# PhatStats_Slim_Enclosure_ESP_Lolin_D32_X.net
KiCad netlist of a schematic drawn in EAGLE
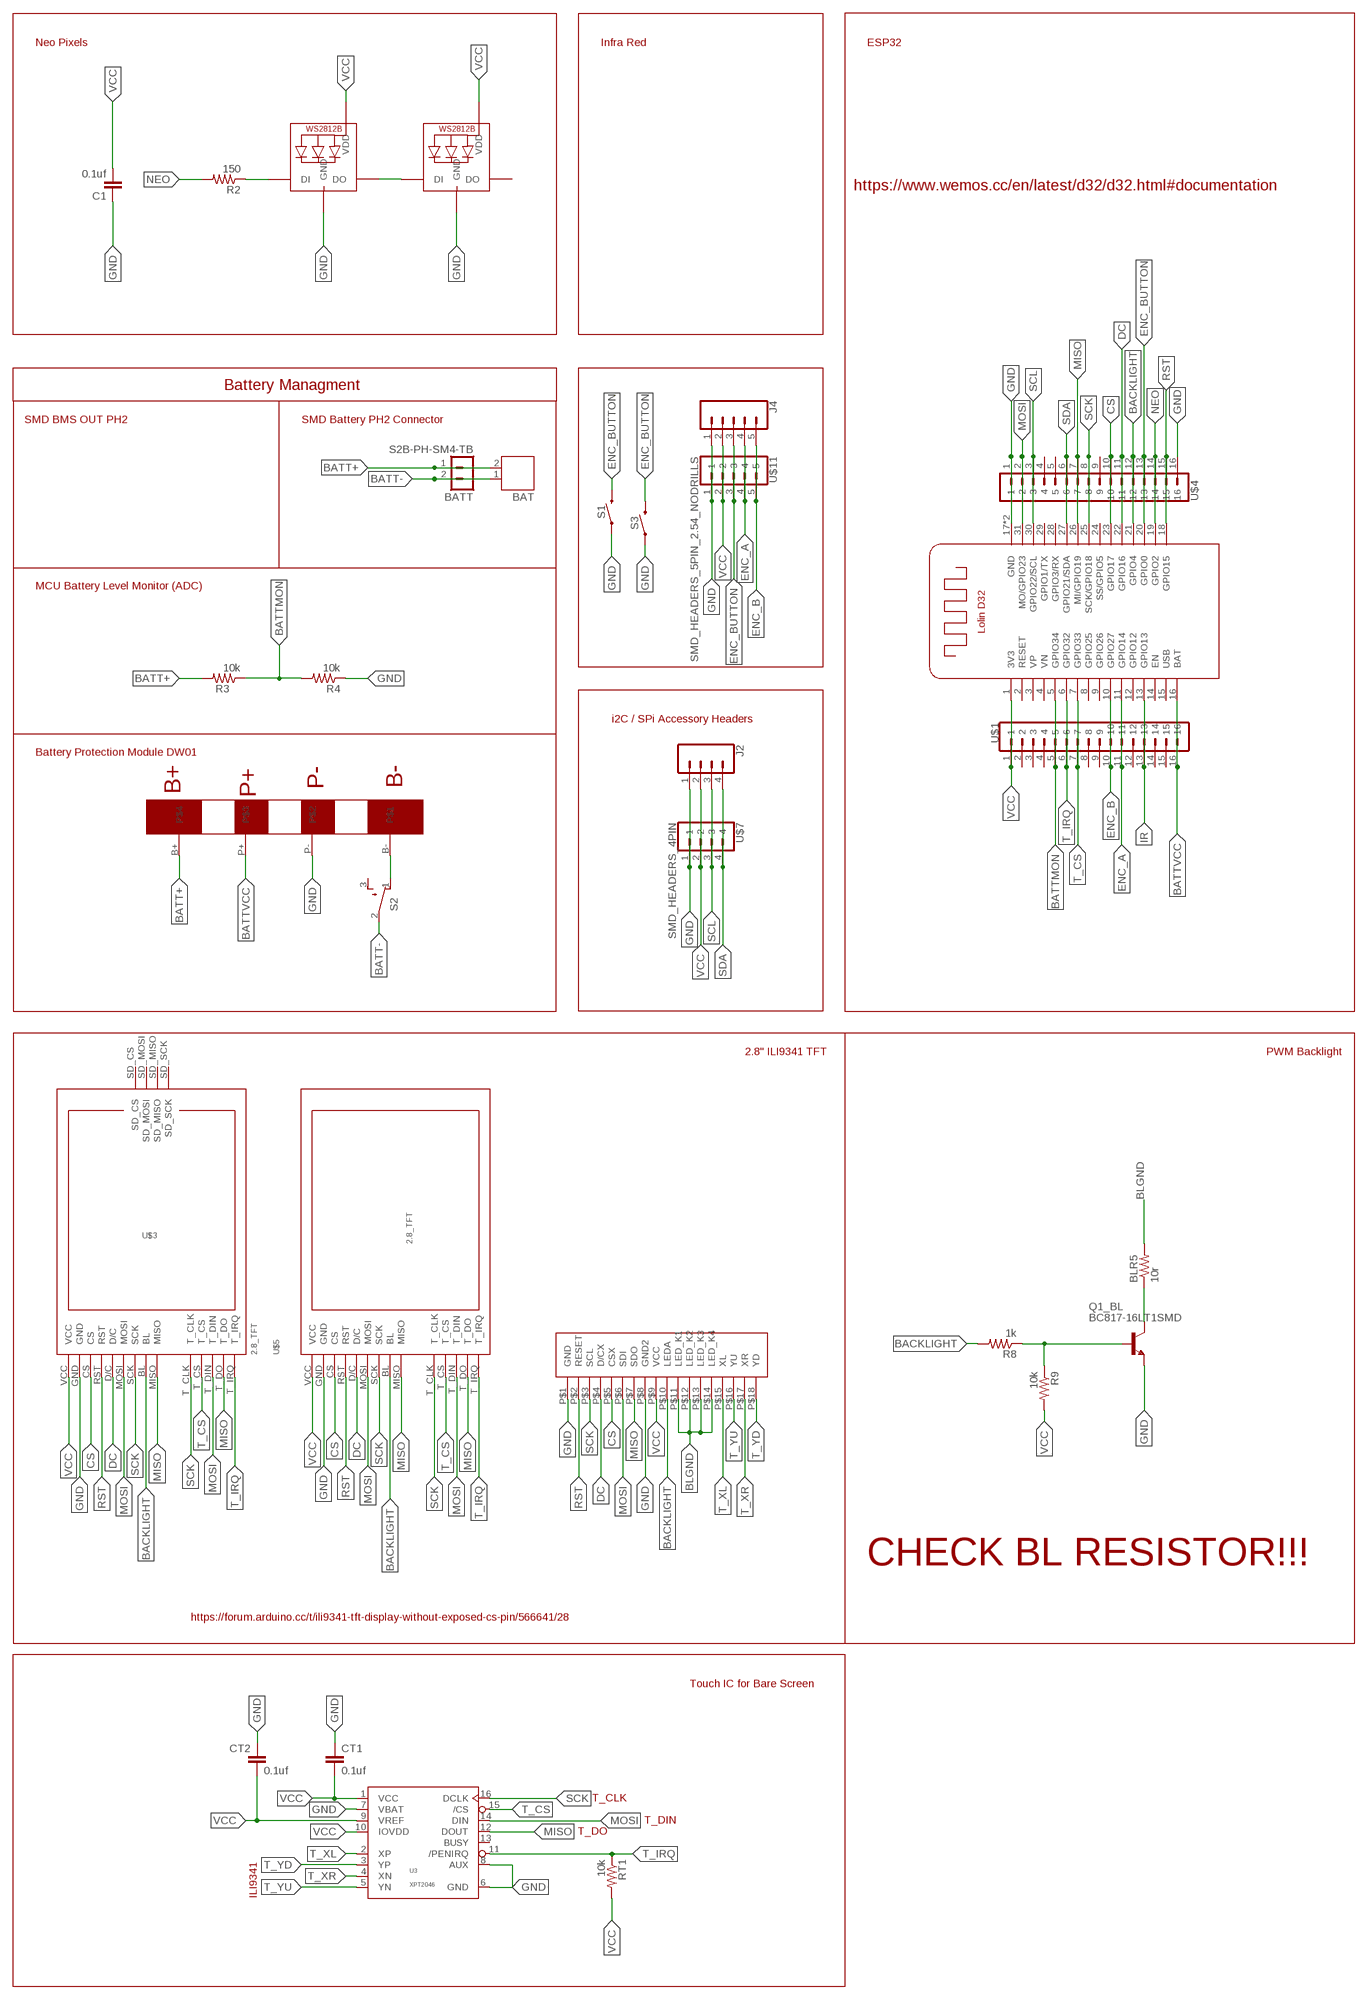
[diagram p0: schematic, sheet 1]

(export (version "E")
  (design (tool "Eeschema 10.0.6"))
  (components
    (comp (ref "0")
      (value "ILI9341-2.8")
      (footprint "eagle-import:ILI9341-2.8")
      (libsource (lib "eagle-import") (part "ILI9341-2.8"))
    )
    (comp (ref "BAT")
      (value "JST-PH2")
      (footprint "eagle-import:JST-PH2")
      (libsource (lib "eagle-import") (part "JST-PH2"))
    )
    (comp (ref "BATT")
      (value "S2B-PH-SM4-TB")
      (footprint "eagle-import:S2B-PH-SM4-TB")
      (libsource (lib "eagle-import") (part "S2B-PH-SM4-TB"))
    )
    (comp (ref "BLR5")
      (value "10r")
      (footprint "eagle-import:M1206")
      (libsource (lib "eagle-import") (part "R-US_M1206"))
    )
    (comp (ref "BMS")
      (value "DW01BATTERYPROT")
      (footprint "eagle-import:DW01BATTERYPROT")
      (libsource (lib "eagle-import") (part "DW01BATTERYPROT"))
    )
    (comp (ref "C1")
      (value "0.1uf")
      (footprint "eagle-import:C1206")
      (libsource (lib "eagle-import") (part "C-EUC1206"))
    )
    (comp (ref "CT1")
      (value "0.1uf")
      (footprint "eagle-import:C1206")
      (libsource (lib "eagle-import") (part "C-EUC1206"))
    )
    (comp (ref "CT2")
      (value "0.1uf")
      (footprint "eagle-import:C1206")
      (libsource (lib "eagle-import") (part "C-EUC1206"))
    )
    (comp (ref "J2")
      (value "CONN_04PTH")
      (footprint "eagle-import:1X04")
      (libsource (lib "eagle-import") (part "CONN_04PTH"))
    )
    (comp (ref "J4")
      (value "CONN_05")
      (footprint "eagle-import:1X05")
      (libsource (lib "eagle-import") (part "CONN_05"))
    )
    (comp (ref "NEO1")
      (value "WS2812B5050")
      (footprint "eagle-import:WS2812B")
      (libsource (lib "eagle-import") (part "WS2812B5050"))
    )
    (comp (ref "NEO2")
      (value "WS2812B5050")
      (footprint "eagle-import:WS2812B")
      (libsource (lib "eagle-import") (part "WS2812B5050"))
    )
    (comp (ref "Q1_BL")
      (value "BC817-16LT1SMD")
      (footprint "eagle-import:SOT23-BEC")
      (libsource (lib "eagle-import") (part "BC817SMD-16LT1"))
    )
    (comp (ref "R2")
      (value "150")
      (footprint "eagle-import:M1206")
      (libsource (lib "eagle-import") (part "R-US_M1206"))
    )
    (comp (ref "R3")
      (value "10k")
      (footprint "eagle-import:M1206")
      (libsource (lib "eagle-import") (part "R-US_M1206"))
    )
    (comp (ref "R4")
      (value "10k")
      (footprint "eagle-import:M1206")
      (libsource (lib "eagle-import") (part "R-US_M1206"))
    )
    (comp (ref "R8")
      (value "1k")
      (footprint "eagle-import:M1206")
      (libsource (lib "eagle-import") (part "R-US_M1206"))
    )
    (comp (ref "R9")
      (value "10k")
      (footprint "eagle-import:M1206")
      (libsource (lib "eagle-import") (part "R-US_M1206"))
    )
    (comp (ref "RT1")
      (value "10k")
      (footprint "eagle-import:M1206")
      (libsource (lib "eagle-import") (part "R-US_M1206"))
    )
    (comp (ref "S1")
      (value "MOMENTARY-SWITCH-SPST-PTH-6.0MM")
      (footprint "eagle-import:TACTILE_SWITCH_PTH_6.0MM")
      (libsource (lib "eagle-import") (part "MOMENTARY-SWITCH-SPST-PTH-6.0MM"))
    )
    (comp (ref "S2")
      (value "SK-12F14(1P2T)0.5A50VDC3MMPITCH")
      (footprint "eagle-import:SK-12F14(1P2T)0.5A50VDC3MMPITCH")
      (libsource (lib "eagle-import") (part "SK-12F14(1P2T)0.5A50VDC3MMPITCH"))
    )
    (comp (ref "S3")
      (value "MOMENTARY-SWITCH-SPST-SMD-6.2MM-TALL")
      (footprint "eagle-import:TACTILE_SWITCH_SMD_6.2MM_TALL")
      (libsource (lib "eagle-import") (part "MOMENTARY-SWITCH-SPST-SMD-6.2MM-TALL"))
    )
    (comp (ref "U$1")
      (value "SMD_HEADERS_16PIN_2.54_NODRILLSSMD_HEADERS_16PIN")
      (footprint "eagle-import:SMD_HEADERS_16PIN")
      (libsource (lib "eagle-import") (part "SMD_HEADERS_16PIN_2.54_NODRILLSSMD_HEADERS_16PIN"))
    )
    (comp (ref "U$2")
      (value "TML_LOLIND32")
      (footprint "eagle-import:TML_LOLIND32")
      (libsource (lib "eagle-import") (part "TML_LOLIND32"))
    )
    (comp (ref "U$3")
      (value "2.8_TFT")
      (footprint "eagle-import:2.8_TFT")
      (libsource (lib "eagle-import") (part "2.8_TFT"))
    )
    (comp (ref "U$4")
      (value "SMD_HEADERS_16PIN_2.54_NODRILLSSMD_HEADERS_16PIN")
      (footprint "eagle-import:SMD_HEADERS_16PIN")
      (libsource (lib "eagle-import") (part "SMD_HEADERS_16PIN_2.54_NODRILLSSMD_HEADERS_16PIN"))
    )
    (comp (ref "U$5")
      (value "2.8_TFT")
      (footprint "eagle-import:2.8_TFT")
      (libsource (lib "eagle-import") (part "TML_ili9341-2.8_tft-display_PinHeader only_2.8_TFT"))
    )
    (comp (ref "U$7")
      (value "SMD_HEADERS_4PIN")
      (footprint "eagle-import:SMD_HEADERS_4PIN")
      (libsource (lib "eagle-import") (part "SMD_HEADERS_4PIN"))
    )
    (comp (ref "U$11")
      (value "SMD_HEADERS_5PIN_2.54_NODRILLS")
      (footprint "eagle-import:SMD_HEADERS_5PIN")
      (libsource (lib "eagle-import") (part "SMD_HEADERS_5PIN_2.54_NODRILLS"))
    )
    (comp (ref "U3")
      (value "XPT2046")
      (footprint "eagle-import:TSSOP-16")
      (fields (field (name "MF") "Xptek"))
      (libsource (lib "eagle-import") (part "XPT2046"))
    )
  )
  (nets
    (net (code "1") (name "/USB") (class "Default")
      (node (ref "U$2") (pin "15") (pinfunction "USB_15") (pintype "power_in"))
    )
    (net (code "2") (name "BACKLIGHT") (class "Default")
      (node (ref "0") (pin "P$10") (pinfunction "LEDA_P$10") (pintype "bidirectional"))
      (node (ref "R8") (pin "2") (pinfunction "2_2") (pintype "passive"))
      (node (ref "U$2") (pin "21") (pinfunction "GPIO4_21") (pintype "bidirectional"))
      (node (ref "U$3") (pin "BL") (pinfunction "BL_BL") (pintype "bidirectional"))
      (node (ref "U$4") (pin "12") (pinfunction "12_12") (pintype "passive"))
      (node (ref "U$5") (pin "BL") (pinfunction "BL_BL") (pintype "bidirectional"))
    )
    (net (code "3") (name "BATT+") (class "Default")
      (node (ref "BAT") (pin "2") (pinfunction "2_2") (pintype "passive"))
      (node (ref "BATT") (pin "1") (pinfunction "1_1") (pintype "passive"))
      (node (ref "BMS") (pin "B+") (pinfunction "P$4_B+") (pintype "bidirectional"))
      (node (ref "R3") (pin "2") (pinfunction "2_2") (pintype "passive"))
    )
    (net (code "4") (name "BATT-") (class "Default")
      (node (ref "BAT") (pin "1") (pinfunction "1_1") (pintype "passive"))
      (node (ref "BATT") (pin "2") (pinfunction "2_2") (pintype "passive"))
      (node (ref "S2") (pin "2") (pinfunction "P_2") (pintype "passive"))
    )
    (net (code "5") (name "BATTMON") (class "Default")
      (node (ref "R3") (pin "1") (pinfunction "1_1") (pintype "passive"))
      (node (ref "R4") (pin "2") (pinfunction "2_2") (pintype "passive"))
      (node (ref "U$1") (pin "5") (pinfunction "5_5") (pintype "passive"))
      (node (ref "U$2") (pin "5") (pinfunction "GPIO34_5") (pintype "input"))
    )
    (net (code "6") (name "BATTVCC") (class "Default")
      (node (ref "BMS") (pin "P+") (pinfunction "P$3_P+") (pintype "bidirectional"))
      (node (ref "U$1") (pin "16") (pinfunction "16_16") (pintype "passive"))
      (node (ref "U$2") (pin "16") (pinfunction "BAT_16") (pintype "power_in"))
    )
    (net (code "7") (name "BLGND") (class "Default")
      (node (ref "0") (pin "P$11") (pinfunction "LED_K1_P$11") (pintype "bidirectional"))
      (node (ref "0") (pin "P$12") (pinfunction "LED_K2_P$12") (pintype "bidirectional"))
      (node (ref "0") (pin "P$13") (pinfunction "LED_K3_P$13") (pintype "bidirectional"))
      (node (ref "0") (pin "P$14") (pinfunction "LED_K4_P$14") (pintype "bidirectional"))
      (node (ref "BLR5") (pin "2") (pinfunction "2_2") (pintype "passive"))
    )
    (net (code "8") (name "CS") (class "Default")
      (node (ref "0") (pin "P$5") (pinfunction "CSX_P$5") (pintype "bidirectional"))
      (node (ref "U$2") (pin "23") (pinfunction "GPIO17_23") (pintype "bidirectional"))
      (node (ref "U$3") (pin "CS") (pinfunction "CS_CS") (pintype "bidirectional"))
      (node (ref "U$4") (pin "10") (pinfunction "10_10") (pintype "passive"))
      (node (ref "U$5") (pin "CS") (pinfunction "CS_CS") (pintype "bidirectional"))
    )
    (net (code "9") (name "DC") (class "Default")
      (node (ref "0") (pin "P$4") (pinfunction "D/CX_P$4") (pintype "bidirectional"))
      (node (ref "U$2") (pin "22") (pinfunction "GPIO16_22") (pintype "bidirectional"))
      (node (ref "U$3") (pin "D/C") (pinfunction "D/C_D/C") (pintype "bidirectional"))
      (node (ref "U$4") (pin "11") (pinfunction "11_11") (pintype "passive"))
      (node (ref "U$5") (pin "D/C") (pinfunction "D/C_D/C") (pintype "bidirectional"))
    )
    (net (code "10") (name "ENC_A") (class "Default")
      (node (ref "J4") (pin "4") (pinfunction "4_4") (pintype "passive"))
      (node (ref "U$1") (pin "11") (pinfunction "11_11") (pintype "passive"))
      (node (ref "U$11") (pin "4") (pinfunction "4_4") (pintype "passive"))
      (node (ref "U$2") (pin "11") (pinfunction "GPIO14_11") (pintype "bidirectional"))
    )
    (net (code "11") (name "ENC_B") (class "Default")
      (node (ref "J4") (pin "5") (pinfunction "5_5") (pintype "passive"))
      (node (ref "U$1") (pin "10") (pinfunction "10_10") (pintype "passive"))
      (node (ref "U$11") (pin "5") (pinfunction "5_5") (pintype "passive"))
      (node (ref "U$2") (pin "10") (pinfunction "GPIO27_10") (pintype "bidirectional"))
    )
    (net (code "12") (name "ENC_BUTTON") (class "Default")
      (node (ref "J4") (pin "3") (pinfunction "3_3") (pintype "passive"))
      (node (ref "S1") (pin "3") (pinfunction "2_3") (pintype "passive"))
      (node (ref "S3") (pin "B2") (pinfunction "2_B2") (pintype "passive"))
      (node (ref "U$11") (pin "3") (pinfunction "3_3") (pintype "passive"))
      (node (ref "U$2") (pin "20") (pinfunction "GPIO0_20") (pintype "bidirectional"))
      (node (ref "U$4") (pin "13") (pinfunction "13_13") (pintype "passive"))
    )
    (net (code "13") (name "GND") (class "Default")
      (node (ref "0") (pin "P$1") (pinfunction "GND_P$1") (pintype "bidirectional"))
      (node (ref "0") (pin "P$8") (pinfunction "GND2_P$8") (pintype "bidirectional"))
      (node (ref "BMS") (pin "P-") (pinfunction "P$2_P-") (pintype "bidirectional"))
      (node (ref "C1") (pin "1") (pinfunction "1_1") (pintype "passive"))
      (node (ref "CT1") (pin "1") (pinfunction "1_1") (pintype "passive"))
      (node (ref "CT2") (pin "1") (pinfunction "1_1") (pintype "passive"))
      (node (ref "J2") (pin "1") (pinfunction "1_1") (pintype "passive"))
      (node (ref "J4") (pin "1") (pinfunction "1_1") (pintype "passive"))
      (node (ref "NEO1") (pin "3-GND") (pinfunction "GND_3-GND") (pintype "power_in"))
      (node (ref "NEO2") (pin "3-GND") (pinfunction "GND_3-GND") (pintype "power_in"))
      (node (ref "Q1_BL") (pin "E") (pinfunction "E_E") (pintype "passive"))
      (node (ref "R4") (pin "1") (pinfunction "1_1") (pintype "passive"))
      (node (ref "S1") (pin "1") (pinfunction "1_1") (pintype "passive"))
      (node (ref "S3") (pin "A2") (pinfunction "1_A2") (pintype "passive"))
      (node (ref "U$11") (pin "1") (pinfunction "1_1") (pintype "passive"))
      (node (ref "U$2") (pin "17") (pinfunction "GND_17") (pintype "power_in"))
      (node (ref "U$2") (pin "32") (pinfunction "GND_32") (pintype "power_in"))
      (node (ref "U$3") (pin "GND") (pinfunction "GND_GND") (pintype "bidirectional"))
      (node (ref "U$4") (pin "1") (pinfunction "1_1") (pintype "passive"))
      (node (ref "U$4") (pin "16") (pinfunction "16_16") (pintype "passive"))
      (node (ref "U$5") (pin "GND") (pinfunction "GND_GND") (pintype "bidirectional"))
      (node (ref "U$7") (pin "1") (pinfunction "1_1") (pintype "passive"))
      (node (ref "U3") (pin "6") (pinfunction "GND_6") (pintype "power_in"))
      (node (ref "U3") (pin "7") (pinfunction "VBAT_7") (pintype "input"))
      (node (ref "U3") (pin "8") (pinfunction "AUX_8") (pintype "input"))
    )
    (net (code "14") (name "IR") (class "Default")
      (node (ref "U$1") (pin "13") (pinfunction "13_13") (pintype "passive"))
      (node (ref "U$2") (pin "13") (pinfunction "GPIO13_13") (pintype "bidirectional"))
    )
    (net (code "15") (name "MISO") (class "Default")
      (node (ref "0") (pin "P$7") (pinfunction "SDO_P$7") (pintype "bidirectional"))
      (node (ref "U$2") (pin "26") (pinfunction "MI/GPIO19_26") (pintype "bidirectional"))
      (node (ref "U$3") (pin "MISO") (pinfunction "MISO_MISO") (pintype "bidirectional"))
      (node (ref "U$3") (pin "T_DO") (pinfunction "T_DO_T_DO") (pintype "bidirectional"))
      (node (ref "U$4") (pin "7") (pinfunction "7_7") (pintype "passive"))
      (node (ref "U$5") (pin "MISO") (pinfunction "MISO_MISO") (pintype "bidirectional"))
      (node (ref "U$5") (pin "T_DO") (pinfunction "T_DO_T_DO") (pintype "bidirectional"))
      (node (ref "U3") (pin "12") (pinfunction "DOUT_12") (pintype "output"))
    )
    (net (code "16") (name "MOSI") (class "Default")
      (node (ref "0") (pin "P$6") (pinfunction "SDI_P$6") (pintype "bidirectional"))
      (node (ref "U$2") (pin "31") (pinfunction "MO/GPIO23_31") (pintype "bidirectional"))
      (node (ref "U$3") (pin "MOSI") (pinfunction "MOSI_MOSI") (pintype "bidirectional"))
      (node (ref "U$3") (pin "T_DIN") (pinfunction "T_DIN_T_DIN") (pintype "bidirectional"))
      (node (ref "U$4") (pin "2") (pinfunction "2_2") (pintype "passive"))
      (node (ref "U$5") (pin "MOSI") (pinfunction "MOSI_MOSI") (pintype "bidirectional"))
      (node (ref "U$5") (pin "T_DIN") (pinfunction "T_DIN_T_DIN") (pintype "bidirectional"))
      (node (ref "U3") (pin "14") (pinfunction "DIN_14") (pintype "input"))
    )
    (net (code "17") (name "NEO") (class "Default")
      (node (ref "R2") (pin "2") (pinfunction "2_2") (pintype "passive"))
      (node (ref "U$2") (pin "19") (pinfunction "GPIO2_19") (pintype "bidirectional"))
      (node (ref "U$4") (pin "14") (pinfunction "14_14") (pintype "passive"))
    )
    (net (code "18") (name "Net-(BLR5-Pad1)") (class "Default")
      (node (ref "BLR5") (pin "1") (pinfunction "1_1") (pintype "passive"))
      (node (ref "Q1_BL") (pin "C") (pinfunction "C_C") (pintype "passive"))
    )
    (net (code "19") (name "Net-(BMS-P$1)") (class "Default")
      (node (ref "BMS") (pin "B-") (pinfunction "P$1_B-") (pintype "bidirectional"))
      (node (ref "S2") (pin "1") (pinfunction "O_1") (pintype "passive"))
    )
    (net (code "20") (name "Net-(NEO1-DI)") (class "Default")
      (node (ref "NEO1") (pin "4-DIN") (pinfunction "DI_4-DIN") (pintype "input"))
      (node (ref "R2") (pin "1") (pinfunction "1_1") (pintype "passive"))
    )
    (net (code "21") (name "Net-(NEO1-DO)") (class "Default")
      (node (ref "NEO1") (pin "2-DOUT") (pinfunction "DO_2-DOUT") (pintype "output"))
      (node (ref "NEO2") (pin "4-DIN") (pinfunction "DI_4-DIN") (pintype "input"))
    )
    (net (code "22") (name "Net-(Q1_BL-PadB)") (class "Default")
      (node (ref "Q1_BL") (pin "B") (pinfunction "B_B") (pintype "passive"))
      (node (ref "R8") (pin "1") (pinfunction "1_1") (pintype "passive"))
      (node (ref "R9") (pin "1") (pinfunction "1_1") (pintype "passive"))
    )
    (net (code "23") (name "RST") (class "Default")
      (node (ref "0") (pin "P$2") (pinfunction "RESET_P$2") (pintype "bidirectional"))
      (node (ref "U$2") (pin "18") (pinfunction "GPIO15_18") (pintype "bidirectional"))
      (node (ref "U$3") (pin "RST") (pinfunction "RST_RST") (pintype "bidirectional"))
      (node (ref "U$4") (pin "15") (pinfunction "15_15") (pintype "passive"))
      (node (ref "U$5") (pin "RST") (pinfunction "RST_RST") (pintype "bidirectional"))
    )
    (net (code "24") (name "SCK") (class "Default")
      (node (ref "0") (pin "P$3") (pinfunction "SCL_P$3") (pintype "bidirectional"))
      (node (ref "U$2") (pin "25") (pinfunction "SCK/GPIO18_25") (pintype "bidirectional"))
      (node (ref "U$3") (pin "SCK") (pinfunction "SCK_SCK") (pintype "bidirectional"))
      (node (ref "U$3") (pin "T_CLK") (pinfunction "T_CLK_T_CLK") (pintype "bidirectional"))
      (node (ref "U$4") (pin "8") (pinfunction "8_8") (pintype "passive"))
      (node (ref "U$5") (pin "SCK") (pinfunction "SCK_SCK") (pintype "bidirectional"))
      (node (ref "U$5") (pin "T_CLK") (pinfunction "T_CLK_T_CLK") (pintype "bidirectional"))
      (node (ref "U3") (pin "16") (pinfunction "DCLK_16") (pintype "input"))
    )
    (net (code "25") (name "SCL") (class "Default")
      (node (ref "J2") (pin "3") (pinfunction "3_3") (pintype "passive"))
      (node (ref "U$2") (pin "30") (pinfunction "GPIO22/SCL_30") (pintype "bidirectional"))
      (node (ref "U$4") (pin "3") (pinfunction "3_3") (pintype "passive"))
      (node (ref "U$7") (pin "3") (pinfunction "3_3") (pintype "passive"))
    )
    (net (code "26") (name "SDA") (class "Default")
      (node (ref "J2") (pin "4") (pinfunction "4_4") (pintype "passive"))
      (node (ref "U$2") (pin "27") (pinfunction "GPIO21/SDA_27") (pintype "bidirectional"))
      (node (ref "U$4") (pin "6") (pinfunction "6_6") (pintype "passive"))
      (node (ref "U$7") (pin "4") (pinfunction "4_4") (pintype "passive"))
    )
    (net (code "27") (name "T_CS") (class "Default")
      (node (ref "U$1") (pin "7") (pinfunction "7_7") (pintype "passive"))
      (node (ref "U$2") (pin "7") (pinfunction "GPIO33_7") (pintype "bidirectional"))
      (node (ref "U$3") (pin "T_CS") (pinfunction "T_CS_T_CS") (pintype "bidirectional"))
      (node (ref "U$5") (pin "T_CS") (pinfunction "T_CS_T_CS") (pintype "bidirectional"))
      (node (ref "U3") (pin "15") (pinfunction "/CS_15") (pintype "input"))
    )
    (net (code "28") (name "T_IRQ") (class "Default")
      (node (ref "RT1") (pin "1") (pinfunction "1_1") (pintype "passive"))
      (node (ref "U$1") (pin "6") (pinfunction "6_6") (pintype "passive"))
      (node (ref "U$2") (pin "6") (pinfunction "GPIO32_6") (pintype "bidirectional"))
      (node (ref "U$3") (pin "T_IRQ") (pinfunction "T_IRQ_T_IRQ") (pintype "bidirectional"))
      (node (ref "U$5") (pin "T_IRQ") (pinfunction "T_IRQ_T_IRQ") (pintype "bidirectional"))
      (node (ref "U3") (pin "11") (pinfunction "/PENIRQ_11") (pintype "output"))
    )
    (net (code "29") (name "T_XL") (class "Default")
      (node (ref "0") (pin "P$15") (pinfunction "XL_P$15") (pintype "bidirectional"))
      (node (ref "U3") (pin "2") (pinfunction "XP_2") (pintype "input"))
    )
    (net (code "30") (name "T_XR") (class "Default")
      (node (ref "0") (pin "P$17") (pinfunction "XR_P$17") (pintype "bidirectional"))
      (node (ref "U3") (pin "4") (pinfunction "XN_4") (pintype "input"))
    )
    (net (code "31") (name "T_YD") (class "Default")
      (node (ref "0") (pin "P$18") (pinfunction "YD_P$18") (pintype "bidirectional"))
      (node (ref "U3") (pin "3") (pinfunction "YP_3") (pintype "input"))
    )
    (net (code "32") (name "T_YU") (class "Default")
      (node (ref "0") (pin "P$16") (pinfunction "YU_P$16") (pintype "bidirectional"))
      (node (ref "U3") (pin "5") (pinfunction "YN_5") (pintype "input"))
    )
    (net (code "33") (name "VCC") (class "Default")
      (node (ref "0") (pin "P$9") (pinfunction "VCC_P$9") (pintype "bidirectional"))
      (node (ref "C1") (pin "2") (pinfunction "2_2") (pintype "passive"))
      (node (ref "CT1") (pin "2") (pinfunction "2_2") (pintype "passive"))
      (node (ref "CT2") (pin "2") (pinfunction "2_2") (pintype "passive"))
      (node (ref "J2") (pin "2") (pinfunction "2_2") (pintype "passive"))
      (node (ref "J4") (pin "2") (pinfunction "2_2") (pintype "passive"))
      (node (ref "NEO1") (pin "1-VDD") (pinfunction "VDD_1-VDD") (pintype "power_in"))
      (node (ref "NEO2") (pin "1-VDD") (pinfunction "VDD_1-VDD") (pintype "power_in"))
      (node (ref "R9") (pin "2") (pinfunction "2_2") (pintype "passive"))
      (node (ref "RT1") (pin "2") (pinfunction "2_2") (pintype "passive"))
      (node (ref "U$1") (pin "1") (pinfunction "1_1") (pintype "passive"))
      (node (ref "U$11") (pin "2") (pinfunction "2_2") (pintype "passive"))
      (node (ref "U$2") (pin "1") (pinfunction "3V3_1") (pintype "power_in"))
      (node (ref "U$3") (pin "VCC") (pinfunction "VCC_VCC") (pintype "bidirectional"))
      (node (ref "U$5") (pin "VCC") (pinfunction "VCC_VCC") (pintype "bidirectional"))
      (node (ref "U$7") (pin "2") (pinfunction "2_2") (pintype "passive"))
      (node (ref "U3") (pin "1") (pinfunction "VCC_1") (pintype "power_in"))
      (node (ref "U3") (pin "10") (pinfunction "IOVDD_10") (pintype "power_in"))
      (node (ref "U3") (pin "9") (pinfunction "VREF_9") (pintype "input"))
    )
    (net (code "34") (name "unconnected-(NEO2-DO-Pad2-DOUT)") (class "Default")
      (node (ref "NEO2") (pin "2-DOUT") (pinfunction "DO_2-DOUT") (pintype "output"))
    )
    (net (code "35") (name "unconnected-(S2-S-Pad3)") (class "Default")
      (node (ref "S2") (pin "3") (pinfunction "S_3") (pintype "passive"))
    )
    (net (code "36") (name "unconnected-(U$1-Pad2)") (class "Default")
      (node (ref "U$1") (pin "2") (pinfunction "2_2") (pintype "passive"))
    )
    (net (code "37") (name "unconnected-(U$1-Pad3)") (class "Default")
      (node (ref "U$1") (pin "3") (pinfunction "3_3") (pintype "passive"))
    )
    (net (code "38") (name "unconnected-(U$1-Pad4)") (class "Default")
      (node (ref "U$1") (pin "4") (pinfunction "4_4") (pintype "passive"))
    )
    (net (code "39") (name "unconnected-(U$1-Pad8)") (class "Default")
      (node (ref "U$1") (pin "8") (pinfunction "8_8") (pintype "passive"))
    )
    (net (code "40") (name "unconnected-(U$1-Pad9)") (class "Default")
      (node (ref "U$1") (pin "9") (pinfunction "9_9") (pintype "passive"))
    )
    (net (code "41") (name "unconnected-(U$1-Pad12)") (class "Default")
      (node (ref "U$1") (pin "12") (pinfunction "12_12") (pintype "passive"))
    )
    (net (code "42") (name "unconnected-(U$1-Pad14)") (class "Default")
      (node (ref "U$1") (pin "14") (pinfunction "14_14") (pintype "passive"))
    )
    (net (code "43") (name "unconnected-(U$1-Pad15)") (class "Default")
      (node (ref "U$1") (pin "15") (pinfunction "15_15") (pintype "passive"))
    )
    (net (code "44") (name "unconnected-(U$2-EN-Pad14)") (class "Default")
      (node (ref "U$2") (pin "14") (pinfunction "EN_14") (pintype "input"))
    )
    (net (code "45") (name "unconnected-(U$2-GPIO1{slash}TX-Pad29)") (class "Default")
      (node (ref "U$2") (pin "29") (pinfunction "GPIO1/TX_29") (pintype "bidirectional"))
    )
    (net (code "46") (name "unconnected-(U$2-GPIO3{slash}RX-Pad28)") (class "Default")
      (node (ref "U$2") (pin "28") (pinfunction "GPIO3/RX_28") (pintype "bidirectional"))
    )
    (net (code "47") (name "unconnected-(U$2-GPIO12-Pad12)") (class "Default")
      (node (ref "U$2") (pin "12") (pinfunction "GPIO12_12") (pintype "bidirectional"))
    )
    (net (code "48") (name "unconnected-(U$2-GPIO25-Pad8)") (class "Default")
      (node (ref "U$2") (pin "8") (pinfunction "GPIO25_8") (pintype "bidirectional"))
    )
    (net (code "49") (name "unconnected-(U$2-GPIO26-Pad9)") (class "Default")
      (node (ref "U$2") (pin "9") (pinfunction "GPIO26_9") (pintype "bidirectional"))
    )
    (net (code "50") (name "unconnected-(U$2-RESET-Pad2)") (class "Default")
      (node (ref "U$2") (pin "2") (pinfunction "RESET_2") (pintype "input"))
    )
    (net (code "51") (name "unconnected-(U$2-SS{slash}GPIO5-Pad24)") (class "Default")
      (node (ref "U$2") (pin "24") (pinfunction "SS/GPIO5_24") (pintype "bidirectional"))
    )
    (net (code "52") (name "unconnected-(U$2-VN-Pad4)") (class "Default")
      (node (ref "U$2") (pin "4") (pinfunction "VN_4") (pintype "no_connect"))
    )
    (net (code "53") (name "unconnected-(U$2-VP-Pad3)") (class "Default")
      (node (ref "U$2") (pin "3") (pinfunction "VP_3") (pintype "no_connect"))
    )
    (net (code "54") (name "unconnected-(U$3-PadSD_CS)") (class "Default")
      (node (ref "U$3") (pin "SD_CS") (pinfunction "SD_CS_SD_CS") (pintype "bidirectional"))
    )
    (net (code "55") (name "unconnected-(U$3-PadSD_MISO)") (class "Default")
      (node (ref "U$3") (pin "SD_MISO") (pinfunction "SD_MISO_SD_MISO") (pintype "bidirectional"))
    )
    (net (code "56") (name "unconnected-(U$3-PadSD_MOSI)") (class "Default")
      (node (ref "U$3") (pin "SD_MOSI") (pinfunction "SD_MOSI_SD_MOSI") (pintype "bidirectional"))
    )
    (net (code "57") (name "unconnected-(U$3-PadSD_SCK)") (class "Default")
      (node (ref "U$3") (pin "SD_SCK") (pinfunction "SD_SCK_SD_SCK") (pintype "bidirectional"))
    )
    (net (code "58") (name "unconnected-(U$4-Pad4)") (class "Default")
      (node (ref "U$4") (pin "4") (pinfunction "4_4") (pintype "passive"))
    )
    (net (code "59") (name "unconnected-(U$4-Pad5)") (class "Default")
      (node (ref "U$4") (pin "5") (pinfunction "5_5") (pintype "passive"))
    )
    (net (code "60") (name "unconnected-(U$4-Pad9)") (class "Default")
      (node (ref "U$4") (pin "9") (pinfunction "9_9") (pintype "passive"))
    )
    (net (code "61") (name "unconnected-(U3-BUSY-Pad13)") (class "Default")
      (node (ref "U3") (pin "13") (pinfunction "BUSY_13") (pintype "output"))
    )
  )
)
